# rtu04_half_bridge.net
KiCad netlist of a schematic drawn in EAGLE
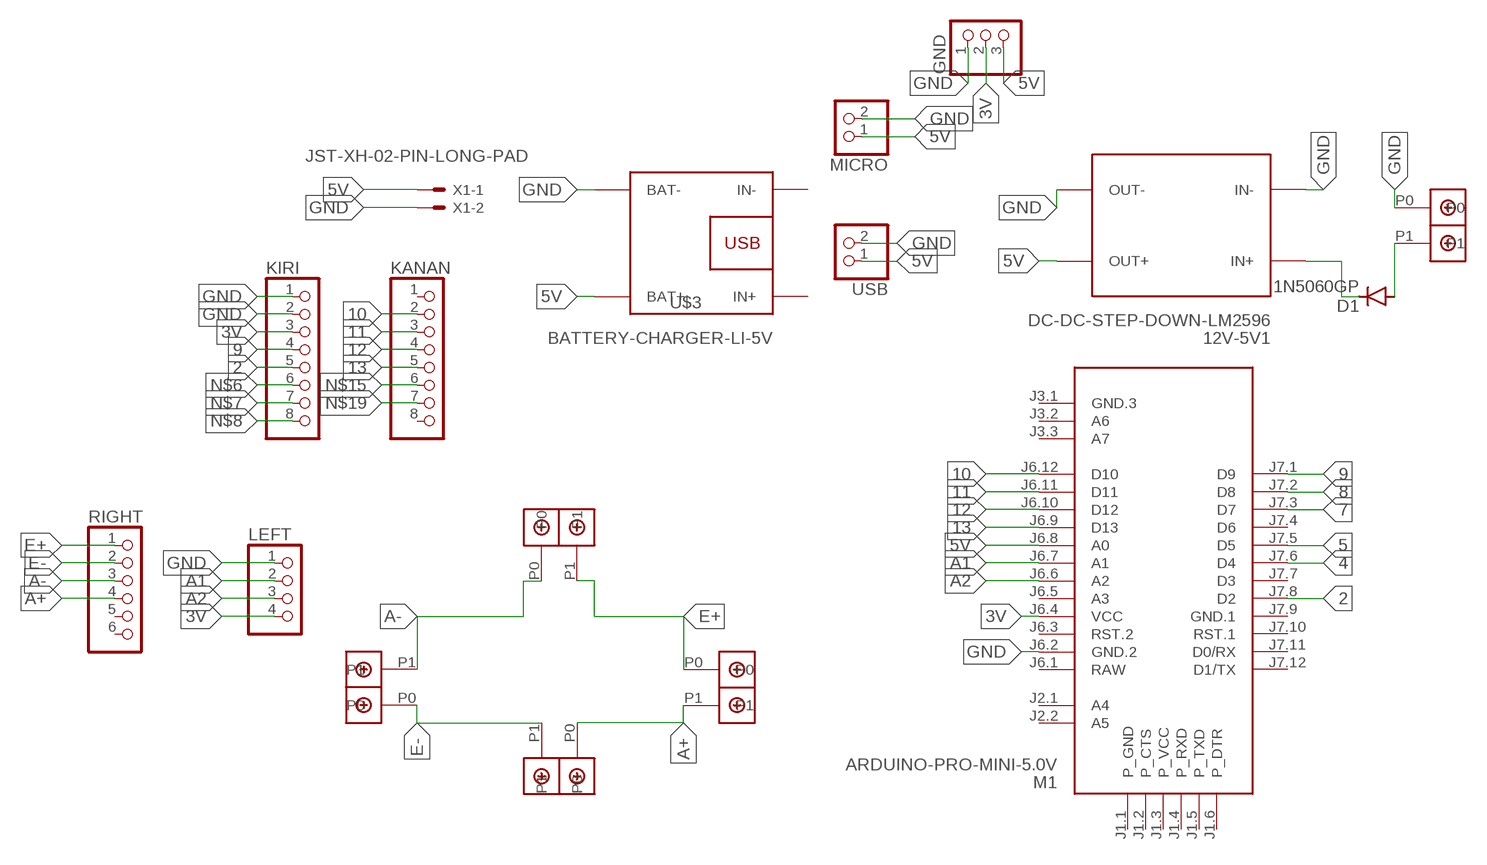
[diagram p0: schematic, sheet 1]

(export (version "E")
  (design (tool "Eeschema 10.0.6"))
  (components
    (comp (ref "12V-5V1")
      (value "DC-DC-STEP-DOWN-LM2596")
      (footprint "eagle-import:DC-DC-STEP-DOWN-LM2596")
      (libsource (lib "eagle-import") (part "DC-DC-STEP-DOWN-LM2596"))
    )
    (comp (ref "D1")
      (value "1N5060GP")
      (footprint "eagle-import:DO15-12")
      (libsource (lib "eagle-import") (part "1N5060GP"))
    )
    (comp (ref "GND")
      (value "PINHD-1X3")
      (footprint "eagle-import:1X03")
      (libsource (lib "eagle-import") (part "PINHD-1X3"))
    )
    (comp (ref "KANAN")
      (value "PINHD-1X8")
      (footprint "eagle-import:1X08")
      (libsource (lib "eagle-import") (part "PINHD-1X8"))
    )
    (comp (ref "KIRI")
      (value "PINHD-1X8")
      (footprint "eagle-import:1X08")
      (libsource (lib "eagle-import") (part "PINHD-1X8"))
    )
    (comp (ref "LEFT")
      (value "PINHD-1X4")
      (footprint "eagle-import:1X04")
      (libsource (lib "eagle-import") (part "PINHD-1X4"))
    )
    (comp (ref "M1")
      (value "ARDUINO-PRO-MINI-5.0V")
      (footprint "eagle-import:ARDUINO-PRO-MINI")
      (libsource (lib "eagle-import") (part "ARDUINO-PRO-MINI-5.0V"))
    )
    (comp (ref "MICRO")
      (value "PINHD-1X2")
      (footprint "eagle-import:1X02")
      (libsource (lib "eagle-import") (part "PINHD-1X2"))
    )
    (comp (ref "RIGHT")
      (value "PINHD-1X6")
      (footprint "eagle-import:1X06")
      (libsource (lib "eagle-import") (part "PINHD-1X6"))
    )
    (comp (ref "U$1")
      (value "DBCONN-1X2")
      (footprint "eagle-import:DBCONN-1X2")
      (libsource (lib "eagle-import") (part "DBCONN-1X2"))
    )
    (comp (ref "U$2")
      (value "DBCONN-1X2")
      (footprint "eagle-import:DBCONN-1X2")
      (libsource (lib "eagle-import") (part "DBCONN-1X2"))
    )
    (comp (ref "U$3")
      (value "BATTERY-CHARGER-LI-5V")
      (footprint "eagle-import:BATTERY-CHARGER-LI-5V")
      (libsource (lib "eagle-import") (part "BATTERY-CHARGER-LI-5V"))
    )
    (comp (ref "U$4")
      (value "DBCONN-1X2")
      (footprint "eagle-import:DBCONN-1X2")
      (libsource (lib "eagle-import") (part "DBCONN-1X2"))
    )
    (comp (ref "U$5")
      (value "DBCONN-1X2")
      (footprint "eagle-import:DBCONN-1X2")
      (libsource (lib "eagle-import") (part "DBCONN-1X2"))
    )
    (comp (ref "U$6")
      (value "DBCONN-1X2")
      (footprint "eagle-import:DBCONN-1X2")
      (libsource (lib "eagle-import") (part "DBCONN-1X2"))
    )
    (comp (ref "USB")
      (value "PINHD-1X2")
      (footprint "eagle-import:1X02")
      (libsource (lib "eagle-import") (part "PINHD-1X2"))
    )
    (comp (ref "X1")
      (value "JST-XH-02-PIN-LONG-PAD")
      (footprint "eagle-import:JST-XH-02-PACKAGE-LONG-PAD")
      (libsource (lib "eagle-import") (part "JST-XH-02-PIN-LONG-PAD"))
    )
  )
  (nets
    (net (code "1") (name "/GND.1") (class "Default")
      (node (ref "M1") (pin "J7.9") (pinfunction "GND.1_J7.9") (pintype "power_in"))
    )
    (net (code "2") (name "/RAW") (class "Default")
      (node (ref "M1") (pin "J6.1") (pinfunction "RAW_J6.1") (pintype "power_in"))
    )
    (net (code "3") (name "2") (class "Default")
      (node (ref "KIRI") (pin "5") (pinfunction "5_5") (pintype "passive"))
      (node (ref "M1") (pin "J7.8") (pinfunction "D2_J7.8") (pintype "bidirectional"))
    )
    (net (code "4") (name "3V") (class "Default")
      (node (ref "GND") (pin "2") (pinfunction "2_2") (pintype "passive"))
      (node (ref "KIRI") (pin "3") (pinfunction "3_3") (pintype "passive"))
      (node (ref "LEFT") (pin "4") (pinfunction "4_4") (pintype "passive"))
      (node (ref "M1") (pin "J6.4") (pinfunction "VCC_J6.4") (pintype "power_in"))
    )
    (net (code "5") (name "4") (class "Default")
      (node (ref "M1") (pin "J7.6") (pinfunction "D4_J7.6") (pintype "bidirectional"))
    )
    (net (code "6") (name "5") (class "Default")
      (node (ref "M1") (pin "J7.5") (pinfunction "D5_J7.5") (pintype "bidirectional"))
    )
    (net (code "7") (name "5V") (class "Default")
      (node (ref "12V-5V1") (pin "OUT+") (pinfunction "OUT+_OUT+") (pintype "bidirectional"))
      (node (ref "GND") (pin "3") (pinfunction "3_3") (pintype "passive"))
      (node (ref "M1") (pin "J6.8") (pinfunction "A0_J6.8") (pintype "bidirectional"))
      (node (ref "MICRO") (pin "1") (pinfunction "1_1") (pintype "passive"))
      (node (ref "U$3") (pin "BAT+") (pinfunction "BAT+_BAT+") (pintype "bidirectional"))
      (node (ref "USB") (pin "1") (pinfunction "1_1") (pintype "passive"))
      (node (ref "X1") (pin "1") (pinfunction "S_1") (pintype "passive"))
    )
    (net (code "8") (name "7") (class "Default")
      (node (ref "M1") (pin "J7.3") (pinfunction "D7_J7.3") (pintype "bidirectional"))
    )
    (net (code "9") (name "8") (class "Default")
      (node (ref "M1") (pin "J7.2") (pinfunction "D8_J7.2") (pintype "bidirectional"))
    )
    (net (code "10") (name "9") (class "Default")
      (node (ref "KIRI") (pin "4") (pinfunction "4_4") (pintype "passive"))
      (node (ref "M1") (pin "J7.1") (pinfunction "D9_J7.1") (pintype "bidirectional"))
    )
    (net (code "11") (name "10") (class "Default")
      (node (ref "KANAN") (pin "2") (pinfunction "2_2") (pintype "passive"))
      (node (ref "M1") (pin "J6.12") (pinfunction "D10_J6.12") (pintype "bidirectional"))
    )
    (net (code "12") (name "11") (class "Default")
      (node (ref "KANAN") (pin "3") (pinfunction "3_3") (pintype "passive"))
      (node (ref "M1") (pin "J6.11") (pinfunction "D11_J6.11") (pintype "bidirectional"))
    )
    (net (code "13") (name "12") (class "Default")
      (node (ref "KANAN") (pin "4") (pinfunction "4_4") (pintype "passive"))
      (node (ref "M1") (pin "J6.10") (pinfunction "D12_J6.10") (pintype "bidirectional"))
    )
    (net (code "14") (name "13") (class "Default")
      (node (ref "KANAN") (pin "5") (pinfunction "5_5") (pintype "passive"))
      (node (ref "M1") (pin "J6.9") (pinfunction "D13_J6.9") (pintype "bidirectional"))
    )
    (net (code "15") (name "A+") (class "Default")
      (node (ref "RIGHT") (pin "4") (pinfunction "4_4") (pintype "passive"))
      (node (ref "U$2") (pin "P0") (pinfunction "P0_P0") (pintype "bidirectional"))
      (node (ref "U$4") (pin "P1") (pinfunction "P1_P1") (pintype "bidirectional"))
    )
    (net (code "16") (name "A-") (class "Default")
      (node (ref "RIGHT") (pin "3") (pinfunction "3_3") (pintype "passive"))
      (node (ref "U$5") (pin "P0") (pinfunction "P0_P0") (pintype "bidirectional"))
      (node (ref "U$6") (pin "P1") (pinfunction "P1_P1") (pintype "bidirectional"))
    )
    (net (code "17") (name "A1") (class "Default")
      (node (ref "LEFT") (pin "2") (pinfunction "2_2") (pintype "passive"))
      (node (ref "M1") (pin "J6.7") (pinfunction "A1_J6.7") (pintype "bidirectional"))
    )
    (net (code "18") (name "A2") (class "Default")
      (node (ref "LEFT") (pin "3") (pinfunction "3_3") (pintype "passive"))
      (node (ref "M1") (pin "J6.6") (pinfunction "A2_J6.6") (pintype "bidirectional"))
    )
    (net (code "19") (name "E+") (class "Default")
      (node (ref "RIGHT") (pin "1") (pinfunction "1_1") (pintype "passive"))
      (node (ref "U$4") (pin "P0") (pinfunction "P0_P0") (pintype "bidirectional"))
      (node (ref "U$5") (pin "P1") (pinfunction "P1_P1") (pintype "bidirectional"))
    )
    (net (code "20") (name "E-") (class "Default")
      (node (ref "RIGHT") (pin "2") (pinfunction "2_2") (pintype "passive"))
      (node (ref "U$2") (pin "P1") (pinfunction "P1_P1") (pintype "bidirectional"))
      (node (ref "U$6") (pin "P0") (pinfunction "P0_P0") (pintype "bidirectional"))
    )
    (net (code "21") (name "GND") (class "Default")
      (node (ref "12V-5V1") (pin "IN-") (pinfunction "IN-_IN-") (pintype "bidirectional"))
      (node (ref "12V-5V1") (pin "OUT-") (pinfunction "OUT-_OUT-") (pintype "bidirectional"))
      (node (ref "GND") (pin "1") (pinfunction "1_1") (pintype "passive"))
      (node (ref "KIRI") (pin "1") (pinfunction "1_1") (pintype "passive"))
      (node (ref "KIRI") (pin "2") (pinfunction "2_2") (pintype "passive"))
      (node (ref "LEFT") (pin "1") (pinfunction "1_1") (pintype "passive"))
      (node (ref "M1") (pin "J6.2") (pinfunction "GND.2_J6.2") (pintype "power_in"))
      (node (ref "MICRO") (pin "2") (pinfunction "2_2") (pintype "passive"))
      (node (ref "U$1") (pin "P0") (pinfunction "P0_P0") (pintype "bidirectional"))
      (node (ref "U$3") (pin "BAT-") (pinfunction "BAT-_BAT-") (pintype "bidirectional"))
      (node (ref "USB") (pin "2") (pinfunction "2_2") (pintype "passive"))
      (node (ref "X1") (pin "2") (pinfunction "S_2") (pintype "passive"))
    )
    (net (code "22") (name "N$6") (class "Default")
      (node (ref "KIRI") (pin "6") (pinfunction "6_6") (pintype "passive"))
    )
    (net (code "23") (name "N$7") (class "Default")
      (node (ref "KIRI") (pin "7") (pinfunction "7_7") (pintype "passive"))
    )
    (net (code "24") (name "N$8") (class "Default")
      (node (ref "KIRI") (pin "8") (pinfunction "8_8") (pintype "passive"))
    )
    (net (code "25") (name "N$15") (class "Default")
      (node (ref "KANAN") (pin "6") (pinfunction "6_6") (pintype "passive"))
    )
    (net (code "26") (name "N$19") (class "Default")
      (node (ref "KANAN") (pin "7") (pinfunction "7_7") (pintype "passive"))
    )
    (net (code "27") (name "Net-(12V-5V1-PadIN+)") (class "Default")
      (node (ref "12V-5V1") (pin "IN+") (pinfunction "IN+_IN+") (pintype "bidirectional"))
      (node (ref "D1") (pin "C") (pinfunction "C_C") (pintype "passive"))
    )
    (net (code "28") (name "Net-(D1-PadA)") (class "Default")
      (node (ref "D1") (pin "A") (pinfunction "A_A") (pintype "passive"))
      (node (ref "U$1") (pin "P1") (pinfunction "P1_P1") (pintype "bidirectional"))
    )
    (net (code "29") (name "unconnected-(KANAN-Pad1)") (class "Default")
      (node (ref "KANAN") (pin "1") (pinfunction "1_1") (pintype "passive"))
    )
    (net (code "30") (name "unconnected-(KANAN-Pad8)") (class "Default")
      (node (ref "KANAN") (pin "8") (pinfunction "8_8") (pintype "passive"))
    )
    (net (code "31") (name "unconnected-(M1-A3-PadJ6.5)") (class "Default")
      (node (ref "M1") (pin "J6.5") (pinfunction "A3_J6.5") (pintype "bidirectional"))
    )
    (net (code "32") (name "unconnected-(M1-A4-PadJ2.1)") (class "Default")
      (node (ref "M1") (pin "J2.1") (pinfunction "A4_J2.1") (pintype "bidirectional"))
    )
    (net (code "33") (name "unconnected-(M1-A5-PadJ2.2)") (class "Default")
      (node (ref "M1") (pin "J2.2") (pinfunction "A5_J2.2") (pintype "bidirectional"))
    )
    (net (code "34") (name "unconnected-(M1-A6-PadJ3.2)") (class "Default")
      (node (ref "M1") (pin "J3.2") (pinfunction "A6_J3.2") (pintype "bidirectional"))
    )
    (net (code "35") (name "unconnected-(M1-A7-PadJ3.3)") (class "Default")
      (node (ref "M1") (pin "J3.3") (pinfunction "A7_J3.3") (pintype "bidirectional"))
    )
    (net (code "36") (name "unconnected-(M1-D0{slash}RX-PadJ7.11)") (class "Default")
      (node (ref "M1") (pin "J7.11") (pinfunction "D0/RX_J7.11") (pintype "bidirectional"))
    )
    (net (code "37") (name "unconnected-(M1-D1{slash}TX-PadJ7.12)") (class "Default")
      (node (ref "M1") (pin "J7.12") (pinfunction "D1/TX_J7.12") (pintype "bidirectional"))
    )
    (net (code "38") (name "unconnected-(M1-D3-PadJ7.7)") (class "Default")
      (node (ref "M1") (pin "J7.7") (pinfunction "D3_J7.7") (pintype "bidirectional"))
    )
    (net (code "39") (name "unconnected-(M1-D6-PadJ7.4)") (class "Default")
      (node (ref "M1") (pin "J7.4") (pinfunction "D6_J7.4") (pintype "bidirectional"))
    )
    (net (code "40") (name "unconnected-(M1-GND.3-PadJ3.1)") (class "Default")
      (node (ref "M1") (pin "J3.1") (pinfunction "GND.3_J3.1") (pintype "bidirectional"))
    )
    (net (code "41") (name "unconnected-(M1-P_CTS-PadJ1.2)") (class "Default")
      (node (ref "M1") (pin "J1.2") (pinfunction "P_CTS_J1.2") (pintype "bidirectional"))
    )
    (net (code "42") (name "unconnected-(M1-P_DTR-PadJ1.6)") (class "Default")
      (node (ref "M1") (pin "J1.6") (pinfunction "P_DTR_J1.6") (pintype "bidirectional"))
    )
    (net (code "43") (name "unconnected-(M1-P_GND-PadJ1.1)") (class "Default")
      (node (ref "M1") (pin "J1.1") (pinfunction "P_GND_J1.1") (pintype "bidirectional"))
    )
    (net (code "44") (name "unconnected-(M1-P_RXD-PadJ1.4)") (class "Default")
      (node (ref "M1") (pin "J1.4") (pinfunction "P_RXD_J1.4") (pintype "bidirectional"))
    )
    (net (code "45") (name "unconnected-(M1-P_TXD-PadJ1.5)") (class "Default")
      (node (ref "M1") (pin "J1.5") (pinfunction "P_TXD_J1.5") (pintype "bidirectional"))
    )
    (net (code "46") (name "unconnected-(M1-P_VCC-PadJ1.3)") (class "Default")
      (node (ref "M1") (pin "J1.3") (pinfunction "P_VCC_J1.3") (pintype "bidirectional"))
    )
    (net (code "47") (name "unconnected-(M1-RST.1-PadJ7.10)") (class "Default")
      (node (ref "M1") (pin "J7.10") (pinfunction "RST.1_J7.10") (pintype "bidirectional"))
    )
    (net (code "48") (name "unconnected-(M1-RST.2-PadJ6.3)") (class "Default")
      (node (ref "M1") (pin "J6.3") (pinfunction "RST.2_J6.3") (pintype "bidirectional"))
    )
    (net (code "49") (name "unconnected-(RIGHT-Pad5)") (class "Default")
      (node (ref "RIGHT") (pin "5") (pinfunction "5_5") (pintype "passive"))
    )
    (net (code "50") (name "unconnected-(RIGHT-Pad6)") (class "Default")
      (node (ref "RIGHT") (pin "6") (pinfunction "6_6") (pintype "passive"))
    )
    (net (code "51") (name "unconnected-(U$3-PadIN+)") (class "Default")
      (node (ref "U$3") (pin "IN+") (pinfunction "IN+_IN+") (pintype "bidirectional"))
    )
    (net (code "52") (name "unconnected-(U$3-PadIN-)") (class "Default")
      (node (ref "U$3") (pin "IN-") (pinfunction "IN-_IN-") (pintype "bidirectional"))
    )
  )
)
